# 2_bootleg-ev-matrix.net
KiCad netlist of a schematic drawn in Altium Designer
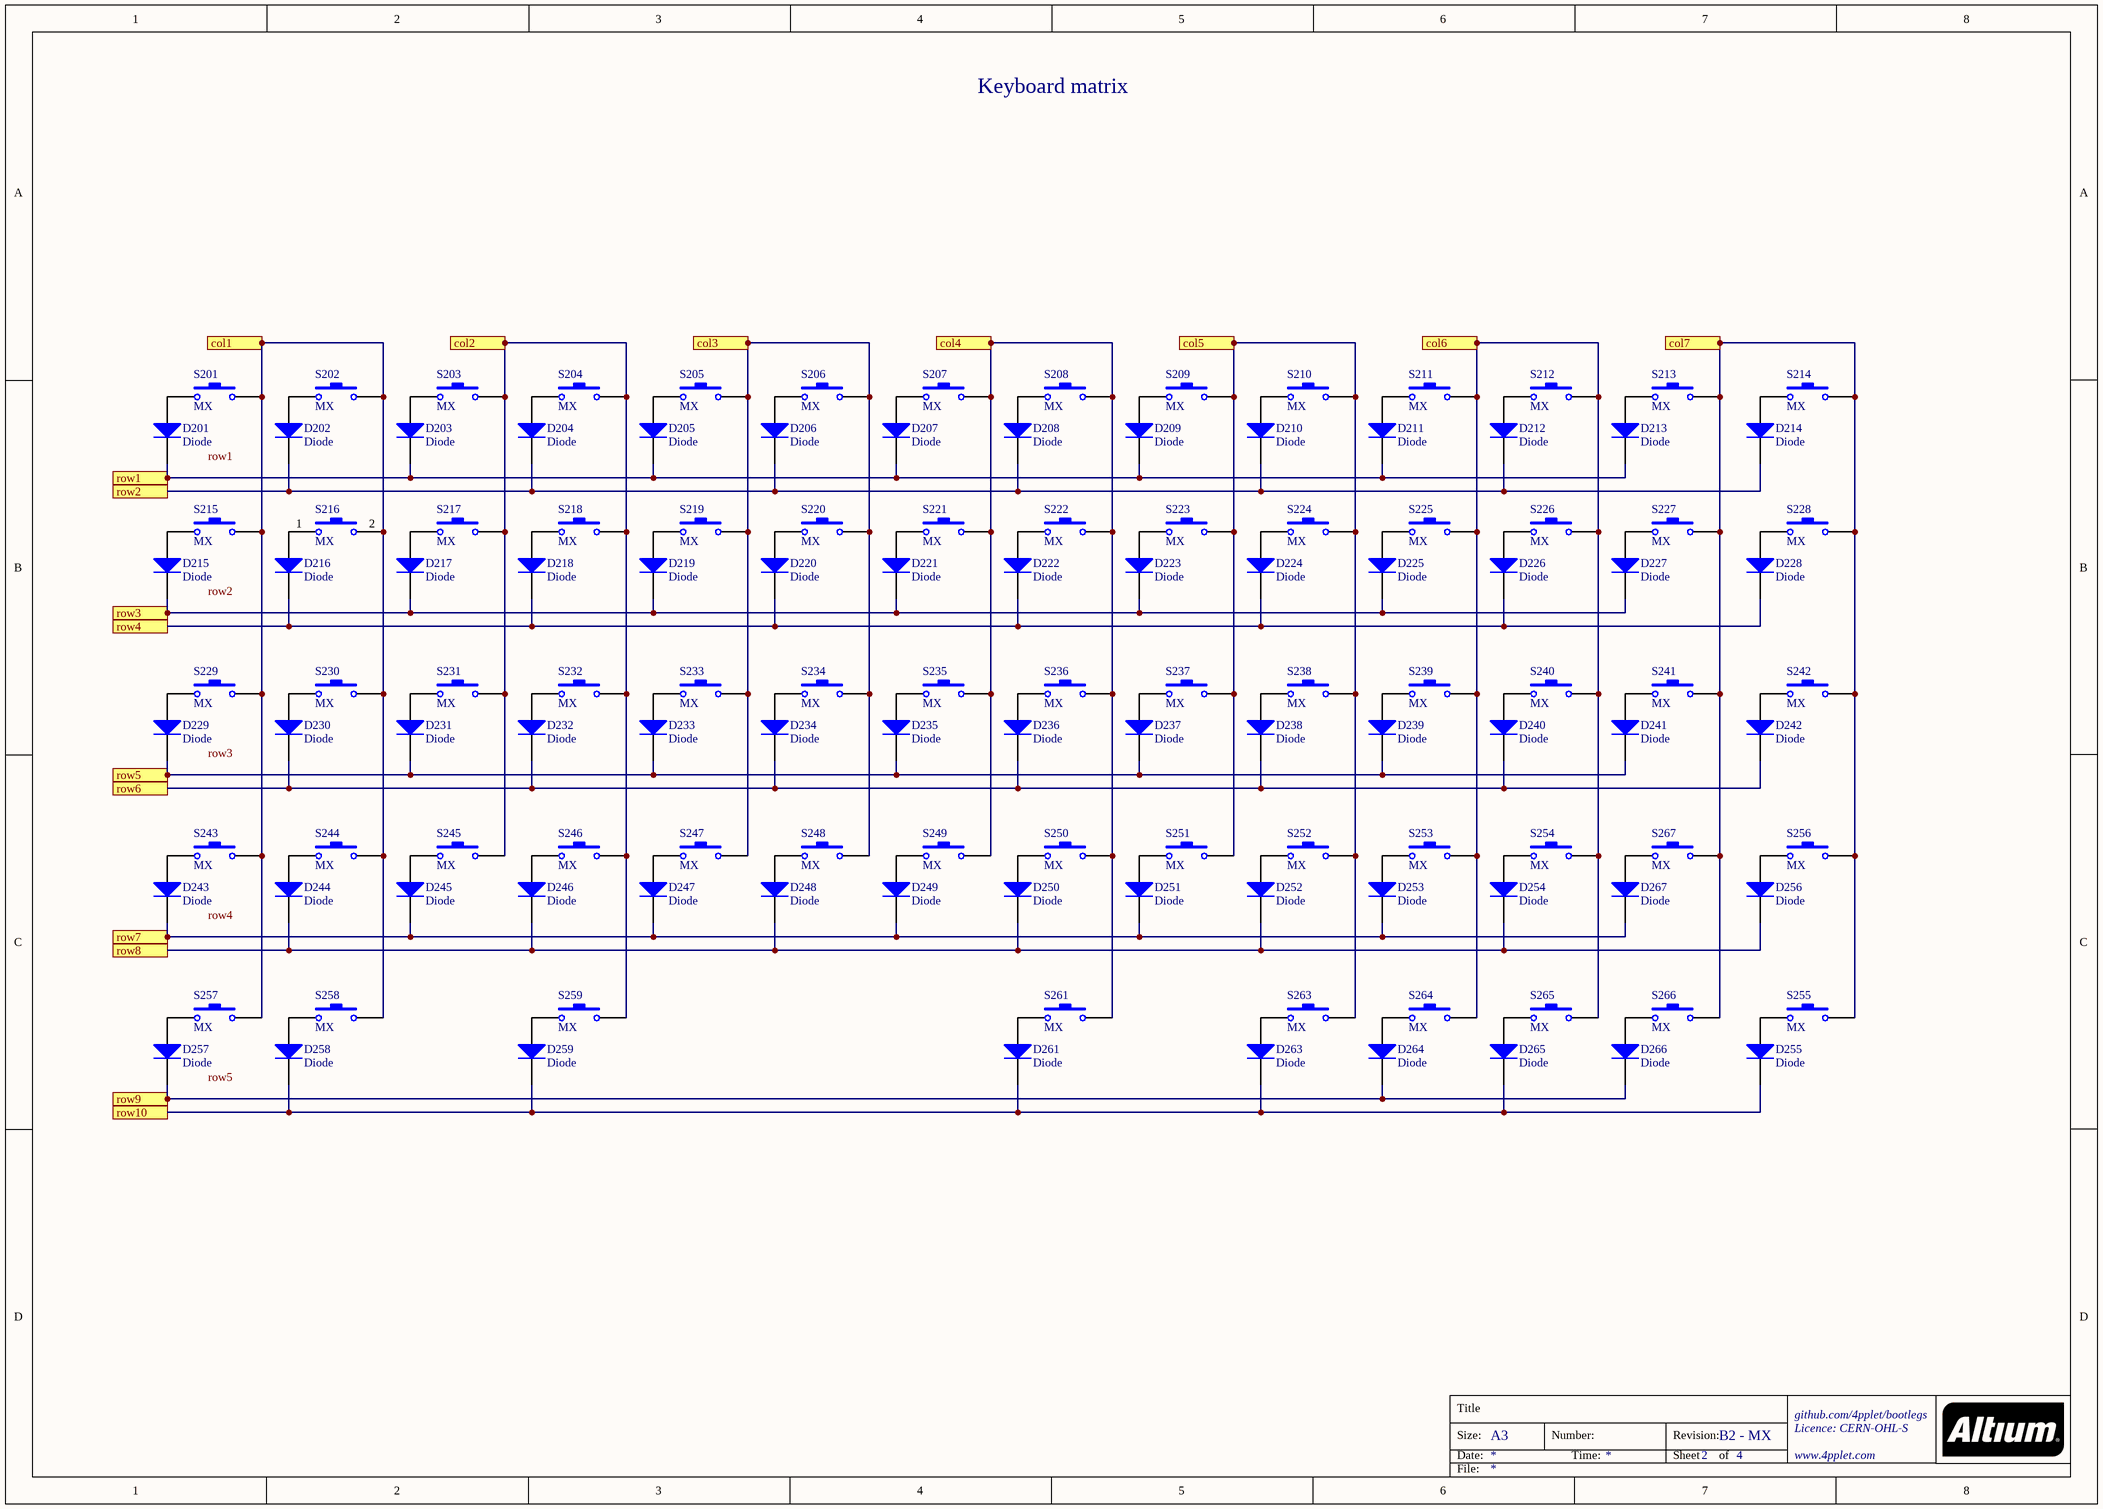
[diagram p0: 2_bootleg-ev-matrix.SchDoc]

(export (version "E")
  (design (tool "Eeschema 10.0.6"))
  (components
    (comp (ref "D201")
      (value "Diode")
      (footprint "SOD-123")
      (description "Default Diode")
      (fields (field (name "LCSC PART #") "C81598") (field (name "MRF.PART") "1N4148W"))
      (libsource (lib "Miscellaneous Devices") (part "Diode"))
    )
    (comp (ref "D202")
      (value "Diode")
      (footprint "SOD-123")
      (description "Default Diode")
      (fields (field (name "LCSC PART #") "C81598") (field (name "MRF.PART") "1N4148W"))
      (libsource (lib "Miscellaneous Devices") (part "Diode"))
    )
    (comp (ref "D203")
      (value "Diode")
      (footprint "SOD-123")
      (description "Default Diode")
      (fields (field (name "LCSC PART #") "C81598") (field (name "MRF.PART") "1N4148W"))
      (libsource (lib "Miscellaneous Devices") (part "Diode"))
    )
    (comp (ref "D204")
      (value "Diode")
      (footprint "SOD-123")
      (description "Default Diode")
      (fields (field (name "LCSC PART #") "C81598") (field (name "MRF.PART") "1N4148W"))
      (libsource (lib "Miscellaneous Devices") (part "Diode"))
    )
    (comp (ref "D205")
      (value "Diode")
      (footprint "SOD-123")
      (description "Default Diode")
      (fields (field (name "LCSC PART #") "C81598") (field (name "MRF.PART") "1N4148W"))
      (libsource (lib "Miscellaneous Devices") (part "Diode"))
    )
    (comp (ref "D206")
      (value "Diode")
      (footprint "SOD-123")
      (description "Default Diode")
      (fields (field (name "LCSC PART #") "C81598") (field (name "MRF.PART") "1N4148W"))
      (libsource (lib "Miscellaneous Devices") (part "Diode"))
    )
    (comp (ref "D207")
      (value "Diode")
      (footprint "SOD-123")
      (description "Default Diode")
      (fields (field (name "LCSC PART #") "C81598") (field (name "MRF.PART") "1N4148W"))
      (libsource (lib "Miscellaneous Devices") (part "Diode"))
    )
    (comp (ref "D208")
      (value "Diode")
      (footprint "SOD-123")
      (description "Default Diode")
      (fields (field (name "LCSC PART #") "C81598") (field (name "MRF.PART") "1N4148W"))
      (libsource (lib "Miscellaneous Devices") (part "Diode"))
    )
    (comp (ref "D209")
      (value "Diode")
      (footprint "SOD-123")
      (description "Default Diode")
      (fields (field (name "LCSC PART #") "C81598") (field (name "MRF.PART") "1N4148W"))
      (libsource (lib "Miscellaneous Devices") (part "Diode"))
    )
    (comp (ref "D210")
      (value "Diode")
      (footprint "SOD-123")
      (description "Default Diode")
      (fields (field (name "LCSC PART #") "C81598") (field (name "MRF.PART") "1N4148W"))
      (libsource (lib "Miscellaneous Devices") (part "Diode"))
    )
    (comp (ref "D211")
      (value "Diode")
      (footprint "SOD-123")
      (description "Default Diode")
      (fields (field (name "LCSC PART #") "C81598") (field (name "MRF.PART") "1N4148W"))
      (libsource (lib "Miscellaneous Devices") (part "Diode"))
    )
    (comp (ref "D212")
      (value "Diode")
      (footprint "SOD-123")
      (description "Default Diode")
      (fields (field (name "LCSC PART #") "C81598") (field (name "MRF.PART") "1N4148W"))
      (libsource (lib "Miscellaneous Devices") (part "Diode"))
    )
    (comp (ref "D213")
      (value "Diode")
      (footprint "SOD-123")
      (description "Default Diode")
      (fields (field (name "LCSC PART #") "C81598") (field (name "MRF.PART") "1N4148W"))
      (libsource (lib "Miscellaneous Devices") (part "Diode"))
    )
    (comp (ref "D214")
      (value "Diode")
      (footprint "SOD-123")
      (description "Default Diode")
      (fields (field (name "LCSC PART #") "C81598") (field (name "MRF.PART") "1N4148W"))
      (libsource (lib "Miscellaneous Devices") (part "Diode"))
    )
    (comp (ref "D215")
      (value "Diode")
      (footprint "SOD-123")
      (description "Default Diode")
      (fields (field (name "LCSC PART #") "C81598") (field (name "MRF.PART") "1N4148W"))
      (libsource (lib "Miscellaneous Devices") (part "Diode"))
    )
    (comp (ref "D216")
      (value "Diode")
      (footprint "SOD-123")
      (description "Default Diode")
      (fields (field (name "LCSC PART #") "C81598") (field (name "MRF.PART") "1N4148W"))
      (libsource (lib "Miscellaneous Devices") (part "Diode"))
    )
    (comp (ref "D217")
      (value "Diode")
      (footprint "SOD-123")
      (description "Default Diode")
      (fields (field (name "LCSC PART #") "C81598") (field (name "MRF.PART") "1N4148W"))
      (libsource (lib "Miscellaneous Devices") (part "Diode"))
    )
    (comp (ref "D218")
      (value "Diode")
      (footprint "SOD-123")
      (description "Default Diode")
      (fields (field (name "LCSC PART #") "C81598") (field (name "MRF.PART") "1N4148W"))
      (libsource (lib "Miscellaneous Devices") (part "Diode"))
    )
    (comp (ref "D219")
      (value "Diode")
      (footprint "SOD-123")
      (description "Default Diode")
      (fields (field (name "LCSC PART #") "C81598") (field (name "MRF.PART") "1N4148W"))
      (libsource (lib "Miscellaneous Devices") (part "Diode"))
    )
    (comp (ref "D220")
      (value "Diode")
      (footprint "SOD-123")
      (description "Default Diode")
      (fields (field (name "LCSC PART #") "C81598") (field (name "MRF.PART") "1N4148W"))
      (libsource (lib "Miscellaneous Devices") (part "Diode"))
    )
    (comp (ref "D221")
      (value "Diode")
      (footprint "SOD-123")
      (description "Default Diode")
      (fields (field (name "LCSC PART #") "C81598") (field (name "MRF.PART") "1N4148W"))
      (libsource (lib "Miscellaneous Devices") (part "Diode"))
    )
    (comp (ref "D222")
      (value "Diode")
      (footprint "SOD-123")
      (description "Default Diode")
      (fields (field (name "LCSC PART #") "C81598") (field (name "MRF.PART") "1N4148W"))
      (libsource (lib "Miscellaneous Devices") (part "Diode"))
    )
    (comp (ref "D223")
      (value "Diode")
      (footprint "SOD-123")
      (description "Default Diode")
      (fields (field (name "LCSC PART #") "C81598") (field (name "MRF.PART") "1N4148W"))
      (libsource (lib "Miscellaneous Devices") (part "Diode"))
    )
    (comp (ref "D224")
      (value "Diode")
      (footprint "SOD-123")
      (description "Default Diode")
      (fields (field (name "LCSC PART #") "C81598") (field (name "MRF.PART") "1N4148W"))
      (libsource (lib "Miscellaneous Devices") (part "Diode"))
    )
    (comp (ref "D225")
      (value "Diode")
      (footprint "SOD-123")
      (description "Default Diode")
      (fields (field (name "LCSC PART #") "C81598") (field (name "MRF.PART") "1N4148W"))
      (libsource (lib "Miscellaneous Devices") (part "Diode"))
    )
    (comp (ref "D226")
      (value "Diode")
      (footprint "SOD-123")
      (description "Default Diode")
      (fields (field (name "LCSC PART #") "C81598") (field (name "MRF.PART") "1N4148W"))
      (libsource (lib "Miscellaneous Devices") (part "Diode"))
    )
    (comp (ref "D227")
      (value "Diode")
      (footprint "SOD-123")
      (description "Default Diode")
      (fields (field (name "LCSC PART #") "C81598") (field (name "MRF.PART") "1N4148W"))
      (libsource (lib "Miscellaneous Devices") (part "Diode"))
    )
    (comp (ref "D228")
      (value "Diode")
      (footprint "SOD-123")
      (description "Default Diode")
      (fields (field (name "LCSC PART #") "C81598") (field (name "MRF.PART") "1N4148W"))
      (libsource (lib "Miscellaneous Devices") (part "Diode"))
    )
    (comp (ref "D229")
      (value "Diode")
      (footprint "SOD-123")
      (description "Default Diode")
      (fields (field (name "LCSC PART #") "C81598") (field (name "MRF.PART") "1N4148W"))
      (libsource (lib "Miscellaneous Devices") (part "Diode"))
    )
    (comp (ref "D230")
      (value "Diode")
      (footprint "SOD-123")
      (description "Default Diode")
      (fields (field (name "LCSC PART #") "C81598") (field (name "MRF.PART") "1N4148W"))
      (libsource (lib "Miscellaneous Devices") (part "Diode"))
    )
    (comp (ref "D231")
      (value "Diode")
      (footprint "SOD-123")
      (description "Default Diode")
      (fields (field (name "LCSC PART #") "C81598") (field (name "MRF.PART") "1N4148W"))
      (libsource (lib "Miscellaneous Devices") (part "Diode"))
    )
    (comp (ref "D232")
      (value "Diode")
      (footprint "SOD-123")
      (description "Default Diode")
      (fields (field (name "LCSC PART #") "C81598") (field (name "MRF.PART") "1N4148W"))
      (libsource (lib "Miscellaneous Devices") (part "Diode"))
    )
    (comp (ref "D233")
      (value "Diode")
      (footprint "SOD-123")
      (description "Default Diode")
      (fields (field (name "LCSC PART #") "C81598") (field (name "MRF.PART") "1N4148W"))
      (libsource (lib "Miscellaneous Devices") (part "Diode"))
    )
    (comp (ref "D234")
      (value "Diode")
      (footprint "SOD-123")
      (description "Default Diode")
      (fields (field (name "LCSC PART #") "C81598") (field (name "MRF.PART") "1N4148W"))
      (libsource (lib "Miscellaneous Devices") (part "Diode"))
    )
    (comp (ref "D235")
      (value "Diode")
      (footprint "SOD-123")
      (description "Default Diode")
      (fields (field (name "LCSC PART #") "C81598") (field (name "MRF.PART") "1N4148W"))
      (libsource (lib "Miscellaneous Devices") (part "Diode"))
    )
    (comp (ref "D236")
      (value "Diode")
      (footprint "SOD-123")
      (description "Default Diode")
      (fields (field (name "LCSC PART #") "C81598") (field (name "MRF.PART") "1N4148W"))
      (libsource (lib "Miscellaneous Devices") (part "Diode"))
    )
    (comp (ref "D237")
      (value "Diode")
      (footprint "SOD-123")
      (description "Default Diode")
      (fields (field (name "LCSC PART #") "C81598") (field (name "MRF.PART") "1N4148W"))
      (libsource (lib "Miscellaneous Devices") (part "Diode"))
    )
    (comp (ref "D238")
      (value "Diode")
      (footprint "SOD-123")
      (description "Default Diode")
      (fields (field (name "LCSC PART #") "C81598") (field (name "MRF.PART") "1N4148W"))
      (libsource (lib "Miscellaneous Devices") (part "Diode"))
    )
    (comp (ref "D239")
      (value "Diode")
      (footprint "SOD-123")
      (description "Default Diode")
      (fields (field (name "LCSC PART #") "C81598") (field (name "MRF.PART") "1N4148W"))
      (libsource (lib "Miscellaneous Devices") (part "Diode"))
    )
    (comp (ref "D240")
      (value "Diode")
      (footprint "SOD-123")
      (description "Default Diode")
      (fields (field (name "LCSC PART #") "C81598") (field (name "MRF.PART") "1N4148W"))
      (libsource (lib "Miscellaneous Devices") (part "Diode"))
    )
    (comp (ref "D241")
      (value "Diode")
      (footprint "SOD-123")
      (description "Default Diode")
      (fields (field (name "LCSC PART #") "C81598") (field (name "MRF.PART") "1N4148W"))
      (libsource (lib "Miscellaneous Devices") (part "Diode"))
    )
    (comp (ref "D242")
      (value "Diode")
      (footprint "SOD-123")
      (description "Default Diode")
      (fields (field (name "LCSC PART #") "C81598") (field (name "MRF.PART") "1N4148W"))
      (libsource (lib "Miscellaneous Devices") (part "Diode"))
    )
    (comp (ref "D243")
      (value "Diode")
      (footprint "SOD-123")
      (description "Default Diode")
      (fields (field (name "LCSC PART #") "C81598") (field (name "MRF.PART") "1N4148W"))
      (libsource (lib "Miscellaneous Devices") (part "Diode"))
    )
    (comp (ref "D244")
      (value "Diode")
      (footprint "SOD-123")
      (description "Default Diode")
      (fields (field (name "LCSC PART #") "C81598") (field (name "MRF.PART") "1N4148W"))
      (libsource (lib "Miscellaneous Devices") (part "Diode"))
    )
    (comp (ref "D245")
      (value "Diode")
      (footprint "SOD-123")
      (description "Default Diode")
      (fields (field (name "LCSC PART #") "C81598") (field (name "MRF.PART") "1N4148W"))
      (libsource (lib "Miscellaneous Devices") (part "Diode"))
    )
    (comp (ref "D246")
      (value "Diode")
      (footprint "SOD-123")
      (description "Default Diode")
      (fields (field (name "LCSC PART #") "C81598") (field (name "MRF.PART") "1N4148W"))
      (libsource (lib "Miscellaneous Devices") (part "Diode"))
    )
    (comp (ref "D247")
      (value "Diode")
      (footprint "SOD-123")
      (description "Default Diode")
      (fields (field (name "LCSC PART #") "C81598") (field (name "MRF.PART") "1N4148W"))
      (libsource (lib "Miscellaneous Devices") (part "Diode"))
    )
    (comp (ref "D248")
      (value "Diode")
      (footprint "SOD-123")
      (description "Default Diode")
      (fields (field (name "LCSC PART #") "C81598") (field (name "MRF.PART") "1N4148W"))
      (libsource (lib "Miscellaneous Devices") (part "Diode"))
    )
    (comp (ref "D249")
      (value "Diode")
      (footprint "SOD-123")
      (description "Default Diode")
      (fields (field (name "LCSC PART #") "C81598") (field (name "MRF.PART") "1N4148W"))
      (libsource (lib "Miscellaneous Devices") (part "Diode"))
    )
    (comp (ref "D250")
      (value "Diode")
      (footprint "SOD-123")
      (description "Default Diode")
      (fields (field (name "LCSC PART #") "C81598") (field (name "MRF.PART") "1N4148W"))
      (libsource (lib "Miscellaneous Devices") (part "Diode"))
    )
    (comp (ref "D251")
      (value "Diode")
      (footprint "SOD-123")
      (description "Default Diode")
      (fields (field (name "LCSC PART #") "C81598") (field (name "MRF.PART") "1N4148W"))
      (libsource (lib "Miscellaneous Devices") (part "Diode"))
    )
    (comp (ref "D252")
      (value "Diode")
      (footprint "SOD-123")
      (description "Default Diode")
      (fields (field (name "LCSC PART #") "C81598") (field (name "MRF.PART") "1N4148W"))
      (libsource (lib "Miscellaneous Devices") (part "Diode"))
    )
    (comp (ref "D253")
      (value "Diode")
      (footprint "SOD-123")
      (description "Default Diode")
      (fields (field (name "LCSC PART #") "C81598") (field (name "MRF.PART") "1N4148W"))
      (libsource (lib "Miscellaneous Devices") (part "Diode"))
    )
    (comp (ref "D254")
      (value "Diode")
      (footprint "SOD-123")
      (description "Default Diode")
      (fields (field (name "LCSC PART #") "C81598") (field (name "MRF.PART") "1N4148W"))
      (libsource (lib "Miscellaneous Devices") (part "Diode"))
    )
    (comp (ref "D255")
      (value "Diode")
      (footprint "SOD-123")
      (description "Default Diode")
      (fields (field (name "LCSC PART #") "C81598") (field (name "MRF.PART") "1N4148W"))
      (libsource (lib "Miscellaneous Devices") (part "Diode"))
    )
    (comp (ref "D256")
      (value "Diode")
      (footprint "SOD-123")
      (description "Default Diode")
      (fields (field (name "LCSC PART #") "C81598") (field (name "MRF.PART") "1N4148W"))
      (libsource (lib "Miscellaneous Devices") (part "Diode"))
    )
    (comp (ref "D257")
      (value "Diode")
      (footprint "SOD-123")
      (description "Default Diode")
      (fields (field (name "LCSC PART #") "C81598") (field (name "MRF.PART") "1N4148W"))
      (libsource (lib "Miscellaneous Devices") (part "Diode"))
    )
    (comp (ref "D258")
      (value "Diode")
      (footprint "SOD-123")
      (description "Default Diode")
      (fields (field (name "LCSC PART #") "C81598") (field (name "MRF.PART") "1N4148W"))
      (libsource (lib "Miscellaneous Devices") (part "Diode"))
    )
    (comp (ref "D259")
      (value "Diode")
      (footprint "SOD-123")
      (description "Default Diode")
      (fields (field (name "LCSC PART #") "C81598") (field (name "MRF.PART") "1N4148W"))
      (libsource (lib "Miscellaneous Devices") (part "Diode"))
    )
    (comp (ref "D261")
      (value "Diode")
      (footprint "SOD-123")
      (description "Default Diode")
      (fields (field (name "LCSC PART #") "C81598") (field (name "MRF.PART") "1N4148W"))
      (libsource (lib "Miscellaneous Devices") (part "Diode"))
    )
    (comp (ref "D263")
      (value "Diode")
      (footprint "SOD-123")
      (description "Default Diode")
      (fields (field (name "LCSC PART #") "C81598") (field (name "MRF.PART") "1N4148W"))
      (libsource (lib "Miscellaneous Devices") (part "Diode"))
    )
    (comp (ref "D264")
      (value "Diode")
      (footprint "SOD-123")
      (description "Default Diode")
      (fields (field (name "LCSC PART #") "C81598") (field (name "MRF.PART") "1N4148W"))
      (libsource (lib "Miscellaneous Devices") (part "Diode"))
    )
    (comp (ref "D265")
      (value "Diode")
      (footprint "SOD-123")
      (description "Default Diode")
      (fields (field (name "LCSC PART #") "C81598") (field (name "MRF.PART") "1N4148W"))
      (libsource (lib "Miscellaneous Devices") (part "Diode"))
    )
    (comp (ref "D266")
      (value "Diode")
      (footprint "SOD-123")
      (description "Default Diode")
      (fields (field (name "LCSC PART #") "C81598") (field (name "MRF.PART") "1N4148W"))
      (libsource (lib "Miscellaneous Devices") (part "Diode"))
    )
    (comp (ref "D267")
      (value "Diode")
      (footprint "SOD-123")
      (description "Default Diode")
      (fields (field (name "LCSC PART #") "C81598") (field (name "MRF.PART") "1N4148W"))
      (libsource (lib "Miscellaneous Devices") (part "Diode"))
    )
    (comp (ref "S201")
      (value "MX")
      (footprint "MX-switch - switched pol")
      (description "Switch")
      (libsource (lib "Miscellaneous Devices") (part "SW-PB"))
    )
    (comp (ref "S202")
      (value "MX")
      (footprint "MX-switch - switched pol - connector")
      (description "Switch")
      (libsource (lib "Miscellaneous Devices") (part "SW-PB"))
    )
    (comp (ref "S203")
      (value "MX")
      (footprint "MX-switch - switched pol")
      (description "Switch")
      (libsource (lib "Miscellaneous Devices") (part "SW-PB"))
    )
    (comp (ref "S204")
      (value "MX")
      (footprint "MX-switch - switched pol")
      (description "Switch")
      (libsource (lib "Miscellaneous Devices") (part "SW-PB"))
    )
    (comp (ref "S205")
      (value "MX")
      (footprint "MX-switch - switched pol")
      (description "Switch")
      (libsource (lib "Miscellaneous Devices") (part "SW-PB"))
    )
    (comp (ref "S206")
      (value "MX")
      (footprint "MX-switch - switched pol")
      (description "Switch")
      (libsource (lib "Miscellaneous Devices") (part "SW-PB"))
    )
    (comp (ref "S207")
      (value "MX")
      (footprint "MX-switch - switched pol")
      (description "Switch")
      (libsource (lib "Miscellaneous Devices") (part "SW-PB"))
    )
    (comp (ref "S208")
      (value "MX")
      (footprint "MX-switch - switched pol")
      (description "Switch")
      (libsource (lib "Miscellaneous Devices") (part "SW-PB"))
    )
    (comp (ref "S209")
      (value "MX")
      (footprint "MX-switch - switched pol")
      (description "Switch")
      (libsource (lib "Miscellaneous Devices") (part "SW-PB"))
    )
    (comp (ref "S210")
      (value "MX")
      (footprint "MX-switch - switched pol")
      (description "Switch")
      (libsource (lib "Miscellaneous Devices") (part "SW-PB"))
    )
    (comp (ref "S211")
      (value "MX")
      (footprint "MX-switch - switched pol")
      (description "Switch")
      (libsource (lib "Miscellaneous Devices") (part "SW-PB"))
    )
    (comp (ref "S212")
      (value "MX")
      (footprint "MX-switch - switched pol")
      (description "Switch")
      (libsource (lib "Miscellaneous Devices") (part "SW-PB"))
    )
    (comp (ref "S213")
      (value "MX")
      (footprint "MX-switch - switched pol")
      (description "Switch")
      (libsource (lib "Miscellaneous Devices") (part "SW-PB"))
    )
    (comp (ref "S214")
      (value "MX")
      (footprint "MX-switch - switched pol")
      (description "Switch")
      (libsource (lib "Miscellaneous Devices") (part "SW-PB"))
    )
    (comp (ref "S215")
      (value "MX")
      (footprint "MX-switch - 1.5U")
      (description "TAB")
      (libsource (lib "Miscellaneous Devices") (part "SW-PB"))
    )
    (comp (ref "S216")
      (value "MX")
      (footprint "MX-switch - switched pol")
      (description "Switch")
      (libsource (lib "") (part "SW-PB_1"))
    )
    (comp (ref "S217")
      (value "MX")
      (footprint "MX-switch - switched pol")
      (description "Switch")
      (libsource (lib "Miscellaneous Devices") (part "SW-PB"))
    )
    (comp (ref "S218")
      (value "MX")
      (footprint "MX-switch - switched pol")
      (description "Switch")
      (libsource (lib "Miscellaneous Devices") (part "SW-PB"))
    )
    (comp (ref "S219")
      (value "MX")
      (footprint "MX-switch - switched pol")
      (description "Switch")
      (libsource (lib "Miscellaneous Devices") (part "SW-PB"))
    )
    (comp (ref "S220")
      (value "MX")
      (footprint "MX-switch - switched pol")
      (description "Switch")
      (libsource (lib "Miscellaneous Devices") (part "SW-PB"))
    )
    (comp (ref "S221")
      (value "MX")
      (footprint "MX-switch - switched pol")
      (description "Switch")
      (libsource (lib "Miscellaneous Devices") (part "SW-PB"))
    )
    (comp (ref "S222")
      (value "MX")
      (footprint "MX-switch - switched pol")
      (description "Switch")
      (libsource (lib "Miscellaneous Devices") (part "SW-PB"))
    )
    (comp (ref "S223")
      (value "MX")
      (footprint "MX-switch - switched pol")
      (description "Switch")
      (libsource (lib "Miscellaneous Devices") (part "SW-PB"))
    )
    (comp (ref "S224")
      (value "MX")
      (footprint "MX-switch - switched pol")
      (description "Switch")
      (libsource (lib "Miscellaneous Devices") (part "SW-PB"))
    )
    (comp (ref "S225")
      (value "MX")
      (footprint "MX-switch - switched pol")
      (description "Switch")
      (libsource (lib "Miscellaneous Devices") (part "SW-PB"))
    )
    (comp (ref "S226")
      (value "MX")
      (footprint "MX-switch")
      (description "Switch")
      (libsource (lib "Miscellaneous Devices") (part "SW-PB"))
    )
    (comp (ref "S227")
      (value "MX")
      (footprint "MX-switch - switched pol")
      (description "Switch")
      (libsource (lib "Miscellaneous Devices") (part "SW-PB"))
    )
    (comp (ref "S228")
      (value "MX")
      (footprint "MX-switch - backspace")
      (description "Switch")
      (libsource (lib "Miscellaneous Devices") (part "SW-PB"))
    )
    (comp (ref "S229")
      (value "MX")
      (footprint "MX-switch - CAPS")
      (description "Switch")
      (libsource (lib "Miscellaneous Devices") (part "SW-PB"))
    )
    (comp (ref "S230")
      (value "MX")
      (footprint "MX-switch - switched pol")
      (description "Switch")
      (libsource (lib "Miscellaneous Devices") (part "SW-PB"))
    )
    (comp (ref "S231")
      (value "MX")
      (footprint "MX-switch - switched pol")
      (description "Switch")
      (libsource (lib "Miscellaneous Devices") (part "SW-PB"))
    )
    (comp (ref "S232")
      (value "MX")
      (footprint "MX-switch - switched pol")
      (description "Switch")
      (libsource (lib "Miscellaneous Devices") (part "SW-PB"))
    )
    (comp (ref "S233")
      (value "MX")
      (footprint "MX-switch - switched pol")
      (description "Switch")
      (libsource (lib "Miscellaneous Devices") (part "SW-PB"))
    )
    (comp (ref "S234")
      (value "MX")
      (footprint "MX-switch - switched pol")
      (description "Switch")
      (libsource (lib "Miscellaneous Devices") (part "SW-PB"))
    )
    (comp (ref "S235")
      (value "MX")
      (footprint "MX-switch - switched pol")
      (description "Switch")
      (libsource (lib "Miscellaneous Devices") (part "SW-PB"))
    )
    (comp (ref "S236")
      (value "MX")
      (footprint "MX-switch - switched pol")
      (description "Switch")
      (libsource (lib "Miscellaneous Devices") (part "SW-PB"))
    )
    (comp (ref "S237")
      (value "MX")
      (footprint "MX-switch - switched pol")
      (description "Switch")
      (libsource (lib "Miscellaneous Devices") (part "SW-PB"))
    )
    (comp (ref "S238")
      (value "MX")
      (footprint "MX-switch - switched pol")
      (description "Switch")
      (libsource (lib "Miscellaneous Devices") (part "SW-PB"))
    )
    (comp (ref "S239")
      (value "MX")
      (footprint "MX-switch")
      (description "Switch")
      (libsource (lib "Miscellaneous Devices") (part "SW-PB"))
    )
    (comp (ref "S240")
      (value "MX")
      (footprint "MX-switch - switched pol")
      (description "Switch")
      (libsource (lib "Miscellaneous Devices") (part "SW-PB"))
    )
    (comp (ref "S241")
      (value "MX")
      (footprint "MX-switch")
      (description "Switch")
      (libsource (lib "Miscellaneous Devices") (part "SW-PB"))
    )
    (comp (ref "S242")
      (value "MX")
      (footprint "MX-switch - 1.5U")
      (description "Switch")
      (libsource (lib "Miscellaneous Devices") (part "SW-PB"))
    )
    (comp (ref "S243")
      (value "MX")
      (footprint "MX-switch - Left shift")
      (description "Switch")
      (libsource (lib "Miscellaneous Devices") (part "SW-PB"))
    )
    (comp (ref "S244")
      (value "MX")
      (footprint "MX-switch")
      (description "Switch")
      (libsource (lib "Miscellaneous Devices") (part "SW-PB"))
    )
    (comp (ref "S245")
      (value "MX")
      (footprint "MX-switch - switched pol")
      (description "Switch")
      (libsource (lib "Miscellaneous Devices") (part "SW-PB"))
    )
    (comp (ref "S246")
      (value "MX")
      (footprint "MX-switch - switched pol")
      (description "Switch")
      (libsource (lib "Miscellaneous Devices") (part "SW-PB"))
    )
    (comp (ref "S247")
      (value "MX")
      (footprint "MX-switch - switched pol")
      (description "Switch")
      (libsource (lib "Miscellaneous Devices") (part "SW-PB"))
    )
    (comp (ref "S248")
      (value "MX")
      (footprint "MX-switch - switched pol")
      (description "Switch")
      (libsource (lib "Miscellaneous Devices") (part "SW-PB"))
    )
    (comp (ref "S249")
      (value "MX")
      (footprint "MX-switch - switched pol")
      (description "Switch")
      (libsource (lib "Miscellaneous Devices") (part "SW-PB"))
    )
    (comp (ref "S250")
      (value "MX")
      (footprint "MX-switch - switched pol")
      (description "Switch")
      (libsource (lib "Miscellaneous Devices") (part "SW-PB"))
    )
    (comp (ref "S251")
      (value "MX")
      (footprint "MX-switch - switched pol")
      (description "Switch")
      (libsource (lib "Miscellaneous Devices") (part "SW-PB"))
    )
    (comp (ref "S252")
      (value "MX")
      (footprint "MX-switch - switched pol")
      (description "Switch")
      (libsource (lib "Miscellaneous Devices") (part "SW-PB"))
    )
    (comp (ref "S253")
      (value "MX")
      (footprint "MX-switch - switched pol")
      (description "Switch")
      (libsource (lib "Miscellaneous Devices") (part "SW-PB"))
    )
    (comp (ref "S254")
      (value "MX")
      (footprint "MX-switch - switched pol")
      (description "Switch")
      (libsource (lib "Miscellaneous Devices") (part "SW-PB"))
    )
    (comp (ref "S255")
      (value "MX")
      (footprint "MX-switch")
      (description "Switch")
      (libsource (lib "Miscellaneous Devices") (part "SW-PB"))
    )
    (comp (ref "S256")
      (value "MX")
      (footprint "MX-switch - Enter")
      (description "Switch")
      (libsource (lib "Miscellaneous Devices") (part "SW-PB"))
    )
    (comp (ref "S257")
      (value "MX")
      (footprint "MX-switch - 1.5u MOD-L")
      (description "Switch")
      (libsource (lib "Miscellaneous Devices") (part "SW-PB"))
    )
    (comp (ref "S258")
      (value "MX")
      (footprint "MX-switch - 1u MOD-L")
      (description "Switch")
      (libsource (lib "Miscellaneous Devices") (part "SW-PB"))
    )
    (comp (ref "S259")
      (value "MX")
      (footprint "MX-switch - 1.5u MOD-L")
      (description "Switch")
      (libsource (lib "Miscellaneous Devices") (part "SW-PB"))
    )
    (comp (ref "S261")
      (value "MX")
      (footprint "MX-switch - Space_V3")
      (description "Switch")
      (libsource (lib "Miscellaneous Devices") (part "SW-PB"))
    )
    (comp (ref "S263")
      (value "MX")
      (footprint "MX-switch")
      (description "Switch")
      (libsource (lib "Miscellaneous Devices") (part "SW-PB"))
    )
    (comp (ref "S264")
      (value "MX")
      (footprint "MX-switch - 1.5u MOD-R")
      (description "Switch")
      (libsource (lib "Miscellaneous Devices") (part "SW-PB"))
    )
    (comp (ref "S265")
      (value "MX")
      (footprint "MX-switch - 1u MOD-R")
      (description "Switch")
      (libsource (lib "Miscellaneous Devices") (part "SW-PB"))
    )
    (comp (ref "S266")
      (value "MX")
      (footprint "MX-switch - 1.5u MOD-R")
      (description "Switch")
      (libsource (lib "Miscellaneous Devices") (part "SW-PB"))
    )
    (comp (ref "S267")
      (value "MX")
      (footprint "MX-switch - right shift")
      (description "Switch")
      (libsource (lib "Miscellaneous Devices") (part "SW-PB"))
    )
  )
  (nets
    (net (code "1") (name "/col1") (class "Default")
      (node (ref "S201") (pin "2") (pinfunction "2_2") (pintype "passive"))
      (node (ref "S202") (pin "2") (pinfunction "2_2") (pintype "passive"))
      (node (ref "S215") (pin "1") (pinfunction "1_1") (pintype "passive"))
      (node (ref "S216") (pin "2") (pinfunction "2_2") (pintype "passive"))
      (node (ref "S229") (pin "2") (pinfunction "2_2") (pintype "passive"))
      (node (ref "S230") (pin "2") (pinfunction "2_2") (pintype "passive"))
      (node (ref "S243") (pin "2") (pinfunction "2_2") (pintype "passive"))
      (node (ref "S244") (pin "2") (pinfunction "2_2") (pintype "passive"))
      (node (ref "S257") (pin "1") (pinfunction "1_1") (pintype "passive"))
      (node (ref "S258") (pin "2") (pinfunction "2_2") (pintype "passive"))
    )
    (net (code "2") (name "/col2") (class "Default")
      (node (ref "S203") (pin "2") (pinfunction "2_2") (pintype "passive"))
      (node (ref "S204") (pin "2") (pinfunction "2_2") (pintype "passive"))
      (node (ref "S217") (pin "2") (pinfunction "2_2") (pintype "passive"))
      (node (ref "S218") (pin "2") (pinfunction "2_2") (pintype "passive"))
      (node (ref "S231") (pin "2") (pinfunction "2_2") (pintype "passive"))
      (node (ref "S232") (pin "2") (pinfunction "2_2") (pintype "passive"))
      (node (ref "S245") (pin "2") (pinfunction "2_2") (pintype "passive"))
      (node (ref "S246") (pin "2") (pinfunction "2_2") (pintype "passive"))
      (node (ref "S259") (pin "2") (pinfunction "2_2") (pintype "passive"))
    )
    (net (code "3") (name "/col3") (class "Default")
      (node (ref "S205") (pin "2") (pinfunction "2_2") (pintype "passive"))
      (node (ref "S206") (pin "2") (pinfunction "2_2") (pintype "passive"))
      (node (ref "S219") (pin "2") (pinfunction "2_2") (pintype "passive"))
      (node (ref "S220") (pin "2") (pinfunction "2_2") (pintype "passive"))
      (node (ref "S233") (pin "2") (pinfunction "2_2") (pintype "passive"))
      (node (ref "S234") (pin "2") (pinfunction "2_2") (pintype "passive"))
      (node (ref "S247") (pin "2") (pinfunction "2_2") (pintype "passive"))
      (node (ref "S248") (pin "2") (pinfunction "2_2") (pintype "passive"))
    )
    (net (code "4") (name "/col4") (class "Default")
      (node (ref "S207") (pin "2") (pinfunction "2_2") (pintype "passive"))
      (node (ref "S208") (pin "2") (pinfunction "2_2") (pintype "passive"))
      (node (ref "S221") (pin "2") (pinfunction "2_2") (pintype "passive"))
      (node (ref "S222") (pin "2") (pinfunction "2_2") (pintype "passive"))
      (node (ref "S235") (pin "2") (pinfunction "2_2") (pintype "passive"))
      (node (ref "S236") (pin "2") (pinfunction "2_2") (pintype "passive"))
      (node (ref "S249") (pin "2") (pinfunction "2_2") (pintype "passive"))
      (node (ref "S250") (pin "2") (pinfunction "2_2") (pintype "passive"))
      (node (ref "S261") (pin "2") (pinfunction "2_2") (pintype "passive"))
    )
    (net (code "5") (name "/col5") (class "Default")
      (node (ref "S209") (pin "2") (pinfunction "2_2") (pintype "passive"))
      (node (ref "S210") (pin "2") (pinfunction "2_2") (pintype "passive"))
      (node (ref "S223") (pin "2") (pinfunction "2_2") (pintype "passive"))
      (node (ref "S224") (pin "2") (pinfunction "2_2") (pintype "passive"))
      (node (ref "S237") (pin "2") (pinfunction "2_2") (pintype "passive"))
      (node (ref "S238") (pin "2") (pinfunction "2_2") (pintype "passive"))
      (node (ref "S251") (pin "2") (pinfunction "2_2") (pintype "passive"))
      (node (ref "S252") (pin "2") (pinfunction "2_2") (pintype "passive"))
      (node (ref "S263") (pin "2") (pinfunction "2_2") (pintype "passive"))
    )
    (net (code "6") (name "/col6") (class "Default")
      (node (ref "S211") (pin "2") (pinfunction "2_2") (pintype "passive"))
      (node (ref "S212") (pin "2") (pinfunction "2_2") (pintype "passive"))
      (node (ref "S225") (pin "2") (pinfunction "2_2") (pintype "passive"))
      (node (ref "S226") (pin "2") (pinfunction "2_2") (pintype "passive"))
      (node (ref "S239") (pin "2") (pinfunction "2_2") (pintype "passive"))
      (node (ref "S240") (pin "2") (pinfunction "2_2") (pintype "passive"))
      (node (ref "S253") (pin "2") (pinfunction "2_2") (pintype "passive"))
      (node (ref "S254") (pin "2") (pinfunction "2_2") (pintype "passive"))
      (node (ref "S264") (pin "1") (pinfunction "1_1") (pintype "passive"))
      (node (ref "S265") (pin "2") (pinfunction "2_2") (pintype "passive"))
    )
    (net (code "7") (name "/col7") (class "Default")
      (node (ref "S213") (pin "2") (pinfunction "2_2") (pintype "passive"))
      (node (ref "S214") (pin "2") (pinfunction "2_2") (pintype "passive"))
      (node (ref "S227") (pin "2") (pinfunction "2_2") (pintype "passive"))
      (node (ref "S228") (pin "1") (pinfunction "1_1") (pintype "passive"))
      (node (ref "S241") (pin "2") (pinfunction "2_2") (pintype "passive"))
      (node (ref "S242") (pin "2") (pinfunction "2_2") (pintype "passive"))
      (node (ref "S255") (pin "2") (pinfunction "2_2") (pintype "passive"))
      (node (ref "S256") (pin "2") (pinfunction "2_2") (pintype "passive"))
      (node (ref "S266") (pin "2") (pinfunction "2_2") (pintype "passive"))
      (node (ref "S267") (pin "2") (pinfunction "2_2") (pintype "passive"))
    )
    (net (code "8") (name "/row1") (class "Default")
      (node (ref "D201") (pin "2") (pinfunction "K_2") (pintype "passive"))
      (node (ref "D203") (pin "2") (pinfunction "K_2") (pintype "passive"))
      (node (ref "D205") (pin "2") (pinfunction "K_2") (pintype "passive"))
      (node (ref "D207") (pin "2") (pinfunction "K_2") (pintype "passive"))
      (node (ref "D209") (pin "2") (pinfunction "K_2") (pintype "passive"))
      (node (ref "D211") (pin "2") (pinfunction "K_2") (pintype "passive"))
      (node (ref "D213") (pin "2") (pinfunction "K_2") (pintype "passive"))
    )
    (net (code "9") (name "/row2") (class "Default")
      (node (ref "D202") (pin "2") (pinfunction "K_2") (pintype "passive"))
      (node (ref "D204") (pin "2") (pinfunction "K_2") (pintype "passive"))
      (node (ref "D206") (pin "2") (pinfunction "K_2") (pintype "passive"))
      (node (ref "D208") (pin "2") (pinfunction "K_2") (pintype "passive"))
      (node (ref "D210") (pin "2") (pinfunction "K_2") (pintype "passive"))
      (node (ref "D212") (pin "2") (pinfunction "K_2") (pintype "passive"))
      (node (ref "D214") (pin "2") (pinfunction "K_2") (pintype "passive"))
    )
    (net (code "10") (name "/row3") (class "Default")
      (node (ref "D215") (pin "2") (pinfunction "K_2") (pintype "passive"))
      (node (ref "D217") (pin "2") (pinfunction "K_2") (pintype "passive"))
      (node (ref "D219") (pin "2") (pinfunction "K_2") (pintype "passive"))
      (node (ref "D221") (pin "2") (pinfunction "K_2") (pintype "passive"))
      (node (ref "D223") (pin "2") (pinfunction "K_2") (pintype "passive"))
      (node (ref "D225") (pin "2") (pinfunction "K_2") (pintype "passive"))
      (node (ref "D227") (pin "2") (pinfunction "K_2") (pintype "passive"))
    )
    (net (code "11") (name "/row4") (class "Default")
      (node (ref "D216") (pin "2") (pinfunction "K_2") (pintype "passive"))
      (node (ref "D218") (pin "2") (pinfunction "K_2") (pintype "passive"))
      (node (ref "D220") (pin "2") (pinfunction "K_2") (pintype "passive"))
      (node (ref "D222") (pin "2") (pinfunction "K_2") (pintype "passive"))
      (node (ref "D224") (pin "2") (pinfunction "K_2") (pintype "passive"))
      (node (ref "D226") (pin "2") (pinfunction "K_2") (pintype "passive"))
      (node (ref "D228") (pin "2") (pinfunction "K_2") (pintype "passive"))
    )
    (net (code "12") (name "/row5") (class "Default")
      (node (ref "D229") (pin "2") (pinfunction "K_2") (pintype "passive"))
      (node (ref "D231") (pin "2") (pinfunction "K_2") (pintype "passive"))
      (node (ref "D233") (pin "2") (pinfunction "K_2") (pintype "passive"))
      (node (ref "D235") (pin "2") (pinfunction "K_2") (pintype "passive"))
      (node (ref "D237") (pin "2") (pinfunction "K_2") (pintype "passive"))
      (node (ref "D239") (pin "2") (pinfunction "K_2") (pintype "passive"))
      (node (ref "D241") (pin "2") (pinfunction "K_2") (pintype "passive"))
    )
    (net (code "13") (name "/row6") (class "Default")
      (node (ref "D230") (pin "2") (pinfunction "K_2") (pintype "passive"))
      (node (ref "D232") (pin "2") (pinfunction "K_2") (pintype "passive"))
      (node (ref "D234") (pin "2") (pinfunction "K_2") (pintype "passive"))
      (node (ref "D236") (pin "2") (pinfunction "K_2") (pintype "passive"))
      (node (ref "D238") (pin "2") (pinfunction "K_2") (pintype "passive"))
      (node (ref "D240") (pin "2") (pinfunction "K_2") (pintype "passive"))
      (node (ref "D242") (pin "2") (pinfunction "K_2") (pintype "passive"))
    )
    (net (code "14") (name "/row7") (class "Default")
      (node (ref "D243") (pin "2") (pinfunction "K_2") (pintype "passive"))
      (node (ref "D245") (pin "2") (pinfunction "K_2") (pintype "passive"))
      (node (ref "D247") (pin "2") (pinfunction "K_2") (pintype "passive"))
      (node (ref "D249") (pin "2") (pinfunction "K_2") (pintype "passive"))
      (node (ref "D251") (pin "2") (pinfunction "K_2") (pintype "passive"))
      (node (ref "D253") (pin "2") (pinfunction "K_2") (pintype "passive"))
      (node (ref "D267") (pin "2") (pinfunction "K_2") (pintype "passive"))
    )
    (net (code "15") (name "/row8") (class "Default")
      (node (ref "D244") (pin "2") (pinfunction "K_2") (pintype "passive"))
      (node (ref "D246") (pin "2") (pinfunction "K_2") (pintype "passive"))
      (node (ref "D248") (pin "2") (pinfunction "K_2") (pintype "passive"))
      (node (ref "D250") (pin "2") (pinfunction "K_2") (pintype "passive"))
      (node (ref "D252") (pin "2") (pinfunction "K_2") (pintype "passive"))
      (node (ref "D254") (pin "2") (pinfunction "K_2") (pintype "passive"))
      (node (ref "D256") (pin "2") (pinfunction "K_2") (pintype "passive"))
    )
    (net (code "16") (name "/row9") (class "Default")
      (node (ref "D257") (pin "2") (pinfunction "K_2") (pintype "passive"))
      (node (ref "D264") (pin "2") (pinfunction "K_2") (pintype "passive"))
      (node (ref "D266") (pin "2") (pinfunction "K_2") (pintype "passive"))
    )
    (net (code "17") (name "/row10") (class "Default")
      (node (ref "D255") (pin "2") (pinfunction "K_2") (pintype "passive"))
      (node (ref "D258") (pin "2") (pinfunction "K_2") (pintype "passive"))
      (node (ref "D259") (pin "2") (pinfunction "K_2") (pintype "passive"))
      (node (ref "D261") (pin "2") (pinfunction "K_2") (pintype "passive"))
      (node (ref "D263") (pin "2") (pinfunction "K_2") (pintype "passive"))
      (node (ref "D265") (pin "2") (pinfunction "K_2") (pintype "passive"))
    )
    (net (code "18") (name "Net-(D201-A)") (class "Default")
      (node (ref "D201") (pin "1") (pinfunction "A_1") (pintype "passive"))
      (node (ref "S201") (pin "1") (pinfunction "1_1") (pintype "passive"))
    )
    (net (code "19") (name "Net-(D202-A)") (class "Default")
      (node (ref "D202") (pin "1") (pinfunction "A_1") (pintype "passive"))
      (node (ref "S202") (pin "1") (pinfunction "1_1") (pintype "passive"))
    )
    (net (code "20") (name "Net-(D203-A)") (class "Default")
      (node (ref "D203") (pin "1") (pinfunction "A_1") (pintype "passive"))
      (node (ref "S203") (pin "1") (pinfunction "1_1") (pintype "passive"))
    )
    (net (code "21") (name "Net-(D204-A)") (class "Default")
      (node (ref "D204") (pin "1") (pinfunction "A_1") (pintype "passive"))
      (node (ref "S204") (pin "1") (pinfunction "1_1") (pintype "passive"))
    )
    (net (code "22") (name "Net-(D205-A)") (class "Default")
      (node (ref "D205") (pin "1") (pinfunction "A_1") (pintype "passive"))
      (node (ref "S205") (pin "1") (pinfunction "1_1") (pintype "passive"))
    )
    (net (code "23") (name "Net-(D206-A)") (class "Default")
      (node (ref "D206") (pin "1") (pinfunction "A_1") (pintype "passive"))
      (node (ref "S206") (pin "1") (pinfunction "1_1") (pintype "passive"))
    )
    (net (code "24") (name "Net-(D207-A)") (class "Default")
      (node (ref "D207") (pin "1") (pinfunction "A_1") (pintype "passive"))
      (node (ref "S207") (pin "1") (pinfunction "1_1") (pintype "passive"))
    )
    (net (code "25") (name "Net-(D208-A)") (class "Default")
      (node (ref "D208") (pin "1") (pinfunction "A_1") (pintype "passive"))
      (node (ref "S208") (pin "1") (pinfunction "1_1") (pintype "passive"))
    )
    (net (code "26") (name "Net-(D209-A)") (class "Default")
      (node (ref "D209") (pin "1") (pinfunction "A_1") (pintype "passive"))
      (node (ref "S209") (pin "1") (pinfunction "1_1") (pintype "passive"))
    )
    (net (code "27") (name "Net-(D210-A)") (class "Default")
      (node (ref "D210") (pin "1") (pinfunction "A_1") (pintype "passive"))
      (node (ref "S210") (pin "1") (pinfunction "1_1") (pintype "passive"))
    )
    (net (code "28") (name "Net-(D211-A)") (class "Default")
      (node (ref "D211") (pin "1") (pinfunction "A_1") (pintype "passive"))
      (node (ref "S211") (pin "1") (pinfunction "1_1") (pintype "passive"))
    )
    (net (code "29") (name "Net-(D212-A)") (class "Default")
      (node (ref "D212") (pin "1") (pinfunction "A_1") (pintype "passive"))
      (node (ref "S212") (pin "1") (pinfunction "1_1") (pintype "passive"))
    )
    (net (code "30") (name "Net-(D213-A)") (class "Default")
      (node (ref "D213") (pin "1") (pinfunction "A_1") (pintype "passive"))
      (node (ref "S213") (pin "1") (pinfunction "1_1") (pintype "passive"))
    )
    (net (code "31") (name "Net-(D214-A)") (class "Default")
      (node (ref "D214") (pin "1") (pinfunction "A_1") (pintype "passive"))
      (node (ref "S214") (pin "1") (pinfunction "1_1") (pintype "passive"))
    )
    (net (code "32") (name "Net-(D215-A)") (class "Default")
      (node (ref "D215") (pin "1") (pinfunction "A_1") (pintype "passive"))
      (node (ref "S215") (pin "2") (pinfunction "2_2") (pintype "passive"))
    )
    (net (code "33") (name "Net-(D216-A)") (class "Default")
      (node (ref "D216") (pin "1") (pinfunction "A_1") (pintype "passive"))
      (node (ref "S216") (pin "1") (pinfunction "1_1") (pintype "passive"))
    )
    (net (code "34") (name "Net-(D217-A)") (class "Default")
      (node (ref "D217") (pin "1") (pinfunction "A_1") (pintype "passive"))
      (node (ref "S217") (pin "1") (pinfunction "1_1") (pintype "passive"))
    )
    (net (code "35") (name "Net-(D218-A)") (class "Default")
      (node (ref "D218") (pin "1") (pinfunction "A_1") (pintype "passive"))
      (node (ref "S218") (pin "1") (pinfunction "1_1") (pintype "passive"))
    )
    (net (code "36") (name "Net-(D219-A)") (class "Default")
      (node (ref "D219") (pin "1") (pinfunction "A_1") (pintype "passive"))
      (node (ref "S219") (pin "1") (pinfunction "1_1") (pintype "passive"))
    )
    (net (code "37") (name "Net-(D220-A)") (class "Default")
      (node (ref "D220") (pin "1") (pinfunction "A_1") (pintype "passive"))
      (node (ref "S220") (pin "1") (pinfunction "1_1") (pintype "passive"))
    )
    (net (code "38") (name "Net-(D221-A)") (class "Default")
      (node (ref "D221") (pin "1") (pinfunction "A_1") (pintype "passive"))
      (node (ref "S221") (pin "1") (pinfunction "1_1") (pintype "passive"))
    )
    (net (code "39") (name "Net-(D222-A)") (class "Default")
      (node (ref "D222") (pin "1") (pinfunction "A_1") (pintype "passive"))
      (node (ref "S222") (pin "1") (pinfunction "1_1") (pintype "passive"))
    )
    (net (code "40") (name "Net-(D223-A)") (class "Default")
      (node (ref "D223") (pin "1") (pinfunction "A_1") (pintype "passive"))
      (node (ref "S223") (pin "1") (pinfunction "1_1") (pintype "passive"))
    )
    (net (code "41") (name "Net-(D224-A)") (class "Default")
      (node (ref "D224") (pin "1") (pinfunction "A_1") (pintype "passive"))
      (node (ref "S224") (pin "1") (pinfunction "1_1") (pintype "passive"))
    )
    (net (code "42") (name "Net-(D225-A)") (class "Default")
      (node (ref "D225") (pin "1") (pinfunction "A_1") (pintype "passive"))
      (node (ref "S225") (pin "1") (pinfunction "1_1") (pintype "passive"))
    )
    (net (code "43") (name "Net-(D226-A)") (class "Default")
      (node (ref "D226") (pin "1") (pinfunction "A_1") (pintype "passive"))
      (node (ref "S226") (pin "1") (pinfunction "1_1") (pintype "passive"))
    )
    (net (code "44") (name "Net-(D227-A)") (class "Default")
      (node (ref "D227") (pin "1") (pinfunction "A_1") (pintype "passive"))
      (node (ref "S227") (pin "1") (pinfunction "1_1") (pintype "passive"))
    )
    (net (code "45") (name "Net-(D228-A)") (class "Default")
      (node (ref "D228") (pin "1") (pinfunction "A_1") (pintype "passive"))
      (node (ref "S228") (pin "2") (pinfunction "2_2") (pintype "passive"))
    )
    (net (code "46") (name "Net-(D229-A)") (class "Default")
      (node (ref "D229") (pin "1") (pinfunction "A_1") (pintype "passive"))
      (node (ref "S229") (pin "1") (pinfunction "1_1") (pintype "passive"))
    )
    (net (code "47") (name "Net-(D230-A)") (class "Default")
      (node (ref "D230") (pin "1") (pinfunction "A_1") (pintype "passive"))
      (node (ref "S230") (pin "1") (pinfunction "1_1") (pintype "passive"))
    )
    (net (code "48") (name "Net-(D231-A)") (class "Default")
      (node (ref "D231") (pin "1") (pinfunction "A_1") (pintype "passive"))
      (node (ref "S231") (pin "1") (pinfunction "1_1") (pintype "passive"))
    )
    (net (code "49") (name "Net-(D232-A)") (class "Default")
      (node (ref "D232") (pin "1") (pinfunction "A_1") (pintype "passive"))
      (node (ref "S232") (pin "1") (pinfunction "1_1") (pintype "passive"))
    )
    (net (code "50") (name "Net-(D233-A)") (class "Default")
      (node (ref "D233") (pin "1") (pinfunction "A_1") (pintype "passive"))
      (node (ref "S233") (pin "1") (pinfunction "1_1") (pintype "passive"))
    )
    (net (code "51") (name "Net-(D234-A)") (class "Default")
      (node (ref "D234") (pin "1") (pinfunction "A_1") (pintype "passive"))
      (node (ref "S234") (pin "1") (pinfunction "1_1") (pintype "passive"))
    )
    (net (code "52") (name "Net-(D235-A)") (class "Default")
      (node (ref "D235") (pin "1") (pinfunction "A_1") (pintype "passive"))
      (node (ref "S235") (pin "1") (pinfunction "1_1") (pintype "passive"))
    )
    (net (code "53") (name "Net-(D236-A)") (class "Default")
      (node (ref "D236") (pin "1") (pinfunction "A_1") (pintype "passive"))
      (node (ref "S236") (pin "1") (pinfunction "1_1") (pintype "passive"))
    )
    (net (code "54") (name "Net-(D237-A)") (class "Default")
      (node (ref "D237") (pin "1") (pinfunction "A_1") (pintype "passive"))
      (node (ref "S237") (pin "1") (pinfunction "1_1") (pintype "passive"))
    )
    (net (code "55") (name "Net-(D238-A)") (class "Default")
      (node (ref "D238") (pin "1") (pinfunction "A_1") (pintype "passive"))
      (node (ref "S238") (pin "1") (pinfunction "1_1") (pintype "passive"))
    )
    (net (code "56") (name "Net-(D239-A)") (class "Default")
      (node (ref "D239") (pin "1") (pinfunction "A_1") (pintype "passive"))
      (node (ref "S239") (pin "1") (pinfunction "1_1") (pintype "passive"))
    )
    (net (code "57") (name "Net-(D240-A)") (class "Default")
      (node (ref "D240") (pin "1") (pinfunction "A_1") (pintype "passive"))
      (node (ref "S240") (pin "1") (pinfunction "1_1") (pintype "passive"))
    )
    (net (code "58") (name "Net-(D241-A)") (class "Default")
      (node (ref "D241") (pin "1") (pinfunction "A_1") (pintype "passive"))
      (node (ref "S241") (pin "1") (pinfunction "1_1") (pintype "passive"))
    )
    (net (code "59") (name "Net-(D242-A)") (class "Default")
      (node (ref "D242") (pin "1") (pinfunction "A_1") (pintype "passive"))
      (node (ref "S242") (pin "1") (pinfunction "1_1") (pintype "passive"))
    )
    (net (code "60") (name "Net-(D243-A)") (class "Default")
      (node (ref "D243") (pin "1") (pinfunction "A_1") (pintype "passive"))
      (node (ref "S243") (pin "1") (pinfunction "1_1") (pintype "passive"))
    )
    (net (code "61") (name "Net-(D244-A)") (class "Default")
      (node (ref "D244") (pin "1") (pinfunction "A_1") (pintype "passive"))
      (node (ref "S244") (pin "1") (pinfunction "1_1") (pintype "passive"))
    )
    (net (code "62") (name "Net-(D245-A)") (class "Default")
      (node (ref "D245") (pin "1") (pinfunction "A_1") (pintype "passive"))
      (node (ref "S245") (pin "1") (pinfunction "1_1") (pintype "passive"))
    )
    (net (code "63") (name "Net-(D246-A)") (class "Default")
      (node (ref "D246") (pin "1") (pinfunction "A_1") (pintype "passive"))
      (node (ref "S246") (pin "1") (pinfunction "1_1") (pintype "passive"))
    )
    (net (code "64") (name "Net-(D247-A)") (class "Default")
      (node (ref "D247") (pin "1") (pinfunction "A_1") (pintype "passive"))
      (node (ref "S247") (pin "1") (pinfunction "1_1") (pintype "passive"))
    )
    (net (code "65") (name "Net-(D248-A)") (class "Default")
      (node (ref "D248") (pin "1") (pinfunction "A_1") (pintype "passive"))
      (node (ref "S248") (pin "1") (pinfunction "1_1") (pintype "passive"))
    )
    (net (code "66") (name "Net-(D249-A)") (class "Default")
      (node (ref "D249") (pin "1") (pinfunction "A_1") (pintype "passive"))
      (node (ref "S249") (pin "1") (pinfunction "1_1") (pintype "passive"))
    )
    (net (code "67") (name "Net-(D250-A)") (class "Default")
      (node (ref "D250") (pin "1") (pinfunction "A_1") (pintype "passive"))
      (node (ref "S250") (pin "1") (pinfunction "1_1") (pintype "passive"))
    )
    (net (code "68") (name "Net-(D251-A)") (class "Default")
      (node (ref "D251") (pin "1") (pinfunction "A_1") (pintype "passive"))
      (node (ref "S251") (pin "1") (pinfunction "1_1") (pintype "passive"))
    )
    (net (code "69") (name "Net-(D252-A)") (class "Default")
      (node (ref "D252") (pin "1") (pinfunction "A_1") (pintype "passive"))
      (node (ref "S252") (pin "1") (pinfunction "1_1") (pintype "passive"))
    )
    (net (code "70") (name "Net-(D253-A)") (class "Default")
      (node (ref "D253") (pin "1") (pinfunction "A_1") (pintype "passive"))
      (node (ref "S253") (pin "1") (pinfunction "1_1") (pintype "passive"))
    )
    (net (code "71") (name "Net-(D254-A)") (class "Default")
      (node (ref "D254") (pin "1") (pinfunction "A_1") (pintype "passive"))
      (node (ref "S254") (pin "1") (pinfunction "1_1") (pintype "passive"))
    )
    (net (code "72") (name "Net-(D255-A)") (class "Default")
      (node (ref "D255") (pin "1") (pinfunction "A_1") (pintype "passive"))
      (node (ref "S255") (pin "1") (pinfunction "1_1") (pintype "passive"))
    )
    (net (code "73") (name "Net-(D256-A)") (class "Default")
      (node (ref "D256") (pin "1") (pinfunction "A_1") (pintype "passive"))
      (node (ref "S256") (pin "1") (pinfunction "1_1") (pintype "passive"))
    )
    (net (code "74") (name "Net-(D257-A)") (class "Default")
      (node (ref "D257") (pin "1") (pinfunction "A_1") (pintype "passive"))
      (node (ref "S257") (pin "2") (pinfunction "2_2") (pintype "passive"))
    )
    (net (code "75") (name "Net-(D258-A)") (class "Default")
      (node (ref "D258") (pin "1") (pinfunction "A_1") (pintype "passive"))
      (node (ref "S258") (pin "1") (pinfunction "1_1") (pintype "passive"))
    )
    (net (code "76") (name "Net-(D259-A)") (class "Default")
      (node (ref "D259") (pin "1") (pinfunction "A_1") (pintype "passive"))
      (node (ref "S259") (pin "1") (pinfunction "1_1") (pintype "passive"))
    )
    (net (code "77") (name "Net-(D261-A)") (class "Default")
      (node (ref "D261") (pin "1") (pinfunction "A_1") (pintype "passive"))
      (node (ref "S261") (pin "1") (pinfunction "1_1") (pintype "passive"))
    )
    (net (code "78") (name "Net-(D263-A)") (class "Default")
      (node (ref "D263") (pin "1") (pinfunction "A_1") (pintype "passive"))
      (node (ref "S263") (pin "1") (pinfunction "1_1") (pintype "passive"))
    )
    (net (code "79") (name "Net-(D264-A)") (class "Default")
      (node (ref "D264") (pin "1") (pinfunction "A_1") (pintype "passive"))
      (node (ref "S264") (pin "2") (pinfunction "2_2") (pintype "passive"))
    )
    (net (code "80") (name "Net-(D265-A)") (class "Default")
      (node (ref "D265") (pin "1") (pinfunction "A_1") (pintype "passive"))
      (node (ref "S265") (pin "1") (pinfunction "1_1") (pintype "passive"))
    )
    (net (code "81") (name "Net-(D266-A)") (class "Default")
      (node (ref "D266") (pin "1") (pinfunction "A_1") (pintype "passive"))
      (node (ref "S266") (pin "1") (pinfunction "1_1") (pintype "passive"))
    )
    (net (code "82") (name "Net-(D267-A)") (class "Default")
      (node (ref "D267") (pin "1") (pinfunction "A_1") (pintype "passive"))
      (node (ref "S267") (pin "1") (pinfunction "1_1") (pintype "passive"))
    )
  )
)
